# SL_LCD_SW_LED_2E.net
KiCad netlist of a schematic drawn in Altium Designer
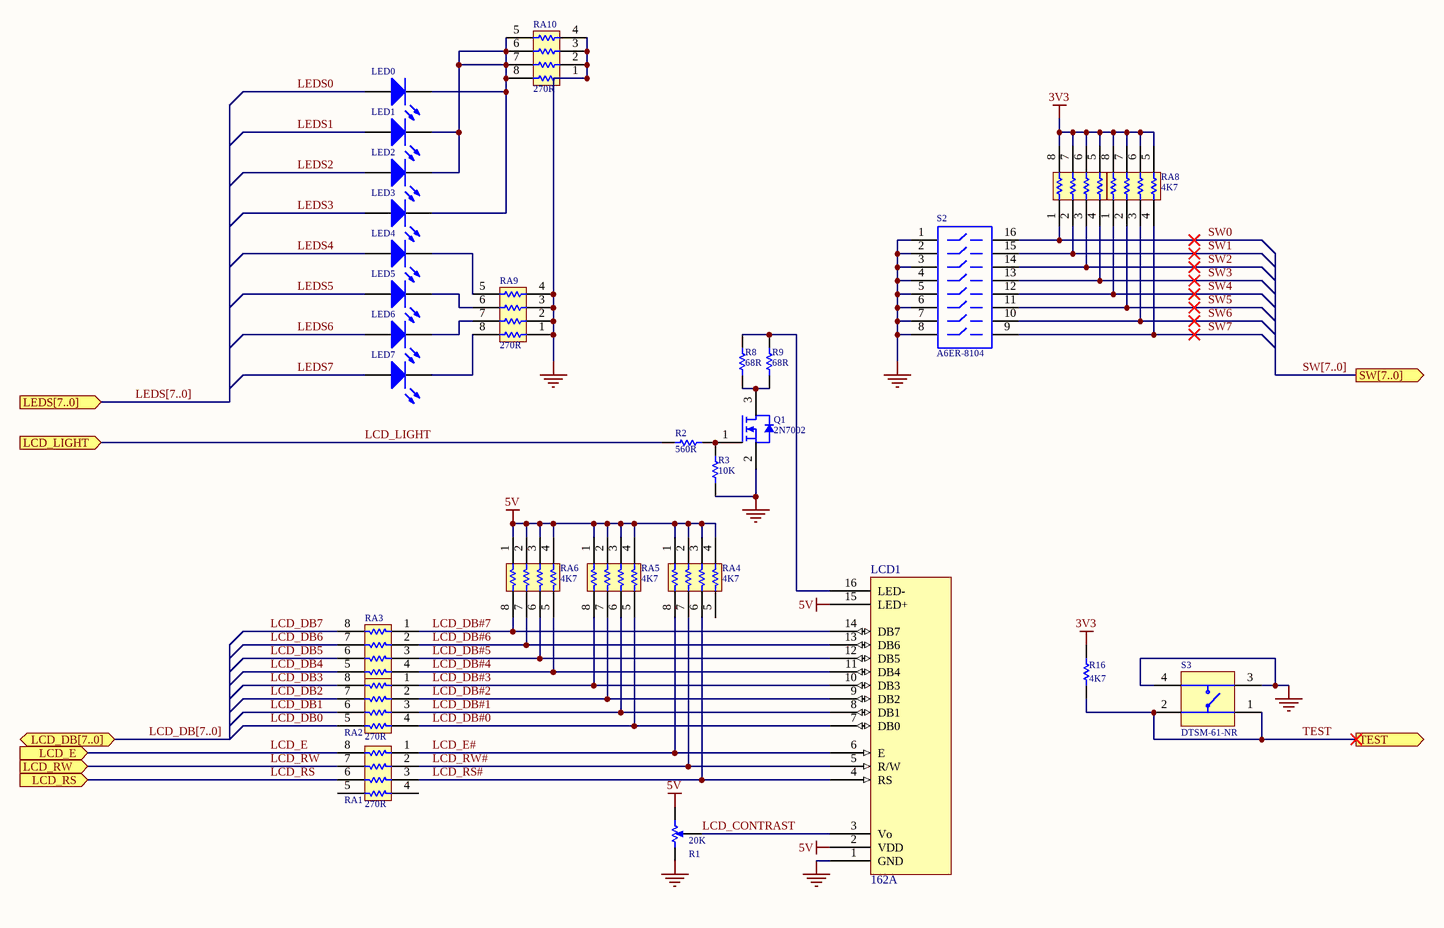
[diagram p0: SL_LCD_SW_LED_2E.SchDoc]

(export (version "E")
  (design (tool "Eeschema 10.0.6"))
  (components
    (comp (ref "LCD1")
      (value "162A")
      (footprint "Spirit_Level_Project:162A")
      (description "16 char * 2 line LCD character display with b/light")
      (libsource (lib "SpiritLevel_2E") (part "162A"))
    )
    (comp (ref "LED0")
      (value "HSMH-C170")
      (footprint "Spirit_Level_Project:SMD _LED")
      (description "Typical RED GaAs SMD LED Agilent make")
      (libsource (lib "SpiritLevel_2E") (part "HSMX-C670"))
    )
    (comp (ref "LED1")
      (value "HSMH-C170")
      (footprint "Spirit_Level_Project:SMD _LED")
      (description "Typical RED GaAs SMD LED Agilent make")
      (libsource (lib "SpiritLevel_2E") (part "HSMX-C670"))
    )
    (comp (ref "LED2")
      (value "HSMH-C170")
      (footprint "Spirit_Level_Project:SMD _LED")
      (description "Typical RED GaAs SMD LED Agilent make")
      (libsource (lib "SpiritLevel_2E") (part "HSMX-C670"))
    )
    (comp (ref "LED3")
      (value "HSMH-C170")
      (footprint "Spirit_Level_Project:SMD _LED")
      (description "Typical RED GaAs SMD LED Agilent make")
      (libsource (lib "SpiritLevel_2E") (part "HSMX-C670"))
    )
    (comp (ref "LED4")
      (value "HSMH-C170")
      (footprint "Spirit_Level_Project:SMD _LED")
      (description "Typical RED GaAs SMD LED Agilent make")
      (libsource (lib "SpiritLevel_2E") (part "HSMX-C670"))
    )
    (comp (ref "LED5")
      (value "HSMH-C170")
      (footprint "Spirit_Level_Project:SMD _LED")
      (description "Typical RED GaAs SMD LED Agilent make")
      (libsource (lib "SpiritLevel_2E") (part "HSMX-C670"))
    )
    (comp (ref "LED6")
      (value "HSMH-C170")
      (footprint "Spirit_Level_Project:SMD _LED")
      (description "Typical RED GaAs SMD LED Agilent make")
      (libsource (lib "SpiritLevel_2E") (part "HSMX-C670"))
    )
    (comp (ref "LED7")
      (value "HSMH-C170")
      (footprint "Spirit_Level_Project:SMD _LED")
      (description "Typical RED GaAs SMD LED Agilent make")
      (libsource (lib "SpiritLevel_2E") (part "HSMX-C670"))
    )
    (comp (ref "Q1")
      (value "2N7002")
      (footprint "Spirit_Level_Project:SO-G3")
      (description "N Channel Mosfet")
      (libsource (lib "SpiritLevel_2E") (part "2N7002"))
    )
    (comp (ref "R1")
      (value "20K")
      (footprint "Spirit_Level_Project:POT4MM-2")
      (description "Square Trimming Potentiometer")
      (libsource (lib "SpiritLevel_2E") (part "RPot SM"))
    )
    (comp (ref "R2")
      (value "560R")
      (footprint "CC2012-0805")
      (description "Resistor")
      (libsource (lib "SpiritLevel_2E") (part "RES"))
    )
    (comp (ref "R3")
      (value "10K")
      (footprint "CC2012-0805")
      (description "Resistor")
      (libsource (lib "SpiritLevel_2E") (part "RES"))
    )
    (comp (ref "R8")
      (value "68R")
      (footprint "CC2012-0805")
      (description "Resistor")
      (libsource (lib "") (part "RES_1"))
    )
    (comp (ref "R9")
      (value "68R")
      (footprint "CC2012-0805")
      (description "Resistor")
      (libsource (lib "") (part "RES_1"))
    )
    (comp (ref "R16")
      (value "4K7")
      (footprint "CC2012-0805")
      (description "Resistor")
      (libsource (lib "SpiritLevel_2E") (part "RES"))
    )
    (comp (ref "RA1")
      (value "270R")
      (footprint "Spirit_Level_Project:MNR34")
      (description "3216x4 Resistor Array")
      (libsource (lib "") (part "MNR34_1"))
    )
    (comp (ref "RA2")
      (value "270R")
      (footprint "Spirit_Level_Project:MNR34")
      (description "3216x4 Resistor Array")
      (libsource (lib "") (part "MNR34_1"))
    )
    (comp (ref "RA3")
      (value "270R")
      (footprint "Spirit_Level_Project:MNR34")
      (description "3216x4 Resistor Array")
      (libsource (lib "") (part "MNR34_1"))
    )
    (comp (ref "RA4")
      (value "4K7")
      (footprint "Spirit_Level_Project:MNR34T")
      (description "3216x4 Resistor Array")
      (libsource (lib "") (part "MNR34_2"))
    )
    (comp (ref "RA5")
      (value "4K7")
      (footprint "Spirit_Level_Project:MNR34T")
      (description "3216x4 Resistor Array")
      (libsource (lib "") (part "MNR34_2"))
    )
    (comp (ref "RA6")
      (value "4K7")
      (footprint "Spirit_Level_Project:MNR34T")
      (description "3216x4 Resistor Array")
      (libsource (lib "") (part "MNR34_2"))
    )
    (comp (ref "RA7")
      (value "4K7")
      (footprint "Spirit_Level_Project:MNR34T")
      (description "3216x4 Resistor Array")
      (libsource (lib "") (part "MNR34_3"))
    )
    (comp (ref "RA8")
      (value "4K7")
      (footprint "Spirit_Level_Project:MNR34T")
      (description "3216x4 Resistor Array")
      (libsource (lib "") (part "MNR34_3"))
    )
    (comp (ref "RA9")
      (value "270R")
      (footprint "Spirit_Level_Project:MNR34T")
      (description "3216x4 Resistor Array")
      (libsource (lib "SpiritLevel_2E") (part "MNR34"))
    )
    (comp (ref "RA10")
      (value "270R")
      (footprint "Spirit_Level_Project:MNR34T")
      (description "3216x4 Resistor Array")
      (libsource (lib "SpiritLevel_2E") (part "MNR34"))
    )
    (comp (ref "S2")
      (value "A6ER-8104")
      (footprint "Spirit_Level_Project:DIP-16-KEY")
      (description "DIP Switch Side actuator long liver Piano Key")
      (libsource (lib "SpiritLevel_2E") (part "A6ER-8104"))
    )
    (comp (ref "S3")
      (value "DTSM-61-NR")
      (footprint "Spirit_Level_Project:B3FS_SWITCH")
      (description "SPNA SMD Keyboard Switch")
      (libsource (lib "SpiritLevel_2E") (part "B3FS"))
    )
  )
  (nets
    (net (code "1") (name "/LCD_CONTRAST") (class "Default")
      (node (ref "LCD1") (pin "3") (pinfunction "Vo_3") (pintype "tri_state"))
      (node (ref "R1") (pin "W") (pintype "passive"))
    )
    (net (code "2") (name "/LCD_DB#0") (class "Default")
      (node (ref "LCD1") (pin "7") (pinfunction "DB0_7") (pintype "bidirectional"))
      (node (ref "RA2") (pin "4") (pintype "passive"))
      (node (ref "RA5") (pin "5") (pintype "passive"))
    )
    (net (code "3") (name "/LCD_DB#1") (class "Default")
      (node (ref "LCD1") (pin "8") (pinfunction "DB1_8") (pintype "bidirectional"))
      (node (ref "RA2") (pin "3") (pintype "passive"))
      (node (ref "RA5") (pin "6") (pintype "passive"))
    )
    (net (code "4") (name "/LCD_DB#2") (class "Default")
      (node (ref "LCD1") (pin "9") (pinfunction "DB2_9") (pintype "bidirectional"))
      (node (ref "RA2") (pin "2") (pintype "passive"))
      (node (ref "RA5") (pin "7") (pintype "passive"))
    )
    (net (code "5") (name "/LCD_DB#3") (class "Default")
      (node (ref "LCD1") (pin "10") (pinfunction "DB3_10") (pintype "bidirectional"))
      (node (ref "RA2") (pin "1") (pintype "passive"))
      (node (ref "RA5") (pin "8") (pintype "passive"))
    )
    (net (code "6") (name "/LCD_DB#4") (class "Default")
      (node (ref "LCD1") (pin "11") (pinfunction "DB4_11") (pintype "bidirectional"))
      (node (ref "RA3") (pin "4") (pintype "passive"))
      (node (ref "RA6") (pin "5") (pintype "passive"))
    )
    (net (code "7") (name "/LCD_DB#5") (class "Default")
      (node (ref "LCD1") (pin "12") (pinfunction "DB5_12") (pintype "bidirectional"))
      (node (ref "RA3") (pin "3") (pintype "passive"))
      (node (ref "RA6") (pin "6") (pintype "passive"))
    )
    (net (code "8") (name "/LCD_DB#6") (class "Default")
      (node (ref "LCD1") (pin "13") (pinfunction "DB6_13") (pintype "bidirectional"))
      (node (ref "RA3") (pin "2") (pintype "passive"))
      (node (ref "RA6") (pin "7") (pintype "passive"))
    )
    (net (code "9") (name "/LCD_DB#7") (class "Default")
      (node (ref "LCD1") (pin "14") (pinfunction "DB7_14") (pintype "bidirectional"))
      (node (ref "RA3") (pin "1") (pintype "passive"))
      (node (ref "RA6") (pin "8") (pintype "passive"))
    )
    (net (code "10") (name "/LCD_DB0") (class "Default") (node (ref "RA2") (pin "5") (pintype "passive")))
    (net (code "11") (name "/LCD_DB1") (class "Default") (node (ref "RA2") (pin "6") (pintype "passive")))
    (net (code "12") (name "/LCD_DB2") (class "Default") (node (ref "RA2") (pin "7") (pintype "passive")))
    (net (code "13") (name "/LCD_DB3") (class "Default") (node (ref "RA2") (pin "8") (pintype "passive")))
    (net (code "14") (name "/LCD_DB4") (class "Default") (node (ref "RA3") (pin "5") (pintype "passive")))
    (net (code "15") (name "/LCD_DB5") (class "Default") (node (ref "RA3") (pin "6") (pintype "passive")))
    (net (code "16") (name "/LCD_DB6") (class "Default") (node (ref "RA3") (pin "7") (pintype "passive")))
    (net (code "17") (name "/LCD_DB7") (class "Default") (node (ref "RA3") (pin "8") (pintype "passive")))
    (net (code "19") (name "/LCD_E") (class "Default") (node (ref "RA1") (pin "8") (pintype "passive")))
    (net (code "20") (name "/LCD_E#") (class "Default")
      (node (ref "LCD1") (pin "6") (pinfunction "E_6") (pintype "input"))
      (node (ref "RA1") (pin "1") (pintype "passive"))
      (node (ref "RA4") (pin "8") (pintype "passive"))
    )
    (net (code "21") (name "/LCD_LIGHT") (class "Default")
      (node (ref "R2") (pin "1") (pinfunction "1_1") (pintype "passive"))
    )
    (net (code "22") (name "/LCD_RS") (class "Default") (node (ref "RA1") (pin "6") (pintype "passive")))
    (net (code "23") (name "/LCD_RS#") (class "Default")
      (node (ref "LCD1") (pin "4") (pinfunction "RS_4") (pintype "input"))
      (node (ref "RA1") (pin "3") (pintype "passive"))
      (node (ref "RA4") (pin "6") (pintype "passive"))
    )
    (net (code "24") (name "/LCD_RW") (class "Default") (node (ref "RA1") (pin "7") (pintype "passive")))
    (net (code "25") (name "/LCD_RW#") (class "Default")
      (node (ref "LCD1") (pin "5") (pinfunction "R/W_5") (pintype "input"))
      (node (ref "RA1") (pin "2") (pintype "passive"))
      (node (ref "RA4") (pin "7") (pintype "passive"))
    )
    (net (code "26") (name "/LEDS0") (class "Default")
      (node (ref "LED0") (pin "1") (pinfunction "A_1") (pintype "passive"))
    )
    (net (code "27") (name "/LEDS1") (class "Default")
      (node (ref "LED1") (pin "1") (pinfunction "A_1") (pintype "passive"))
    )
    (net (code "28") (name "/LEDS2") (class "Default")
      (node (ref "LED2") (pin "1") (pinfunction "A_1") (pintype "passive"))
    )
    (net (code "29") (name "/LEDS3") (class "Default")
      (node (ref "LED3") (pin "1") (pinfunction "A_1") (pintype "passive"))
    )
    (net (code "30") (name "/LEDS4") (class "Default")
      (node (ref "LED4") (pin "1") (pinfunction "A_1") (pintype "passive"))
    )
    (net (code "31") (name "/LEDS5") (class "Default")
      (node (ref "LED5") (pin "1") (pinfunction "A_1") (pintype "passive"))
    )
    (net (code "32") (name "/LEDS6") (class "Default")
      (node (ref "LED6") (pin "1") (pinfunction "A_1") (pintype "passive"))
    )
    (net (code "33") (name "/LEDS7") (class "Default")
      (node (ref "LED7") (pin "1") (pinfunction "A_1") (pintype "passive"))
    )
    (net (code "35") (name "/SW0") (class "Default")
      (node (ref "RA7") (pin "1") (pintype "passive"))
      (node (ref "S2") (pin "16") (pinfunction "16_16") (pintype "passive"))
    )
    (net (code "36") (name "/SW1") (class "Default")
      (node (ref "RA7") (pin "2") (pintype "passive"))
      (node (ref "S2") (pin "15") (pinfunction "15_15") (pintype "passive"))
    )
    (net (code "37") (name "/SW2") (class "Default")
      (node (ref "RA7") (pin "3") (pintype "passive"))
      (node (ref "S2") (pin "14") (pinfunction "14_14") (pintype "passive"))
    )
    (net (code "38") (name "/SW3") (class "Default")
      (node (ref "RA7") (pin "4") (pintype "passive"))
      (node (ref "S2") (pin "13") (pinfunction "13_13") (pintype "passive"))
    )
    (net (code "39") (name "/SW4") (class "Default")
      (node (ref "RA8") (pin "1") (pintype "passive"))
      (node (ref "S2") (pin "12") (pinfunction "12_12") (pintype "passive"))
    )
    (net (code "40") (name "/SW5") (class "Default")
      (node (ref "RA8") (pin "2") (pintype "passive"))
      (node (ref "S2") (pin "11") (pinfunction "11_11") (pintype "passive"))
    )
    (net (code "41") (name "/SW6") (class "Default")
      (node (ref "RA8") (pin "3") (pintype "passive"))
      (node (ref "S2") (pin "10") (pinfunction "10_10") (pintype "passive"))
    )
    (net (code "42") (name "/SW7") (class "Default")
      (node (ref "RA8") (pin "4") (pintype "passive"))
      (node (ref "S2") (pin "9") (pinfunction "9_9") (pintype "passive"))
    )
    (net (code "44") (name "/TEST") (class "Default")
      (node (ref "R16") (pin "2") (pinfunction "2_2") (pintype "passive"))
      (node (ref "S3") (pin "1") (pinfunction "1_1") (pintype "passive"))
      (node (ref "S3") (pin "2") (pinfunction "2_2") (pintype "passive"))
    )
    (net (code "45") (name "3V3") (class "Default")
      (node (ref "R16") (pin "1") (pinfunction "1_1") (pintype "passive"))
      (node (ref "RA7") (pin "5") (pintype "passive"))
      (node (ref "RA7") (pin "6") (pintype "passive"))
      (node (ref "RA7") (pin "7") (pintype "passive"))
      (node (ref "RA7") (pin "8") (pintype "passive"))
      (node (ref "RA8") (pin "5") (pintype "passive"))
      (node (ref "RA8") (pin "6") (pintype "passive"))
      (node (ref "RA8") (pin "7") (pintype "passive"))
      (node (ref "RA8") (pin "8") (pintype "passive"))
    )
    (net (code "46") (name "5V") (class "Default")
      (node (ref "LCD1") (pin "15") (pinfunction "LED+_15") (pintype "power_in"))
      (node (ref "LCD1") (pin "2") (pinfunction "VDD_2") (pintype "power_in"))
      (node (ref "R1") (pin "CW") (pinfunction "+_CW") (pintype "passive"))
      (node (ref "RA4") (pin "1") (pintype "passive"))
      (node (ref "RA4") (pin "2") (pintype "passive"))
      (node (ref "RA4") (pin "3") (pintype "passive"))
      (node (ref "RA4") (pin "4") (pintype "passive"))
      (node (ref "RA5") (pin "1") (pintype "passive"))
      (node (ref "RA5") (pin "2") (pintype "passive"))
      (node (ref "RA5") (pin "3") (pintype "passive"))
      (node (ref "RA5") (pin "4") (pintype "passive"))
      (node (ref "RA6") (pin "1") (pintype "passive"))
      (node (ref "RA6") (pin "2") (pintype "passive"))
      (node (ref "RA6") (pin "3") (pintype "passive"))
      (node (ref "RA6") (pin "4") (pintype "passive"))
    )
    (net (code "47") (name "GND") (class "Default")
      (node (ref "LCD1") (pin "1") (pinfunction "GND_1") (pintype "power_in"))
      (node (ref "Q1") (pin "2") (pintype "passive"))
      (node (ref "R1") (pin "CCW") (pinfunction "-_CCW") (pintype "passive"))
      (node (ref "R3") (pin "1") (pinfunction "1_1") (pintype "passive"))
      (node (ref "RA10") (pin "1") (pintype "passive"))
      (node (ref "RA10") (pin "2") (pintype "passive"))
      (node (ref "RA10") (pin "3") (pintype "passive"))
      (node (ref "RA10") (pin "4") (pintype "passive"))
      (node (ref "RA9") (pin "1") (pintype "passive"))
      (node (ref "RA9") (pin "2") (pintype "passive"))
      (node (ref "RA9") (pin "3") (pintype "passive"))
      (node (ref "RA9") (pin "4") (pintype "passive"))
      (node (ref "S2") (pin "1") (pinfunction "1_1") (pintype "passive"))
      (node (ref "S2") (pin "2") (pinfunction "2_2") (pintype "passive"))
      (node (ref "S2") (pin "3") (pinfunction "3_3") (pintype "passive"))
      (node (ref "S2") (pin "4") (pinfunction "4_4") (pintype "passive"))
      (node (ref "S2") (pin "5") (pinfunction "5_5") (pintype "passive"))
      (node (ref "S2") (pin "6") (pinfunction "6_6") (pintype "passive"))
      (node (ref "S2") (pin "7") (pinfunction "7_7") (pintype "passive"))
      (node (ref "S2") (pin "8") (pinfunction "8_8") (pintype "passive"))
      (node (ref "S3") (pin "3") (pinfunction "3_3") (pintype "passive"))
      (node (ref "S3") (pin "4") (pinfunction "4_4") (pintype "passive"))
    )
    (net (code "48") (name "Net-(LCD1-LED-)") (class "Default")
      (node (ref "LCD1") (pin "16") (pinfunction "LED-_16") (pintype "power_in"))
      (node (ref "R8") (pin "1") (pinfunction "1_1") (pintype "passive"))
      (node (ref "R9") (pin "1") (pinfunction "1_1") (pintype "passive"))
    )
    (net (code "49") (name "Net-(LED0-K)") (class "Default")
      (node (ref "LED0") (pin "2") (pinfunction "K_2") (pintype "passive"))
      (node (ref "LED1") (pin "2") (pinfunction "K_2") (pintype "passive"))
      (node (ref "LED2") (pin "2") (pinfunction "K_2") (pintype "passive"))
      (node (ref "LED3") (pin "2") (pinfunction "K_2") (pintype "passive"))
      (node (ref "RA10") (pin "5") (pintype "passive"))
      (node (ref "RA10") (pin "6") (pintype "passive"))
      (node (ref "RA10") (pin "7") (pintype "passive"))
      (node (ref "RA10") (pin "8") (pintype "passive"))
    )
    (net (code "50") (name "Net-(LED4-K)") (class "Default")
      (node (ref "LED4") (pin "2") (pinfunction "K_2") (pintype "passive"))
      (node (ref "RA9") (pin "5") (pintype "passive"))
    )
    (net (code "51") (name "Net-(LED5-K)") (class "Default")
      (node (ref "LED5") (pin "2") (pinfunction "K_2") (pintype "passive"))
      (node (ref "RA9") (pin "6") (pintype "passive"))
    )
    (net (code "52") (name "Net-(LED6-K)") (class "Default")
      (node (ref "LED6") (pin "2") (pinfunction "K_2") (pintype "passive"))
      (node (ref "RA9") (pin "7") (pintype "passive"))
    )
    (net (code "53") (name "Net-(LED7-K)") (class "Default")
      (node (ref "LED7") (pin "2") (pinfunction "K_2") (pintype "passive"))
      (node (ref "RA9") (pin "8") (pintype "passive"))
    )
    (net (code "54") (name "Net-(Q1-Pad1)") (class "Default")
      (node (ref "Q1") (pin "1") (pintype "passive"))
      (node (ref "R2") (pin "2") (pinfunction "2_2") (pintype "passive"))
      (node (ref "R3") (pin "2") (pinfunction "2_2") (pintype "passive"))
    )
    (net (code "55") (name "Net-(Q1-Pad3)") (class "Default")
      (node (ref "Q1") (pin "3") (pintype "passive"))
      (node (ref "R8") (pin "2") (pinfunction "2_2") (pintype "passive"))
      (node (ref "R9") (pin "2") (pinfunction "2_2") (pintype "passive"))
    )
    (net (code "56") (name "unconnected-(RA1-Pad4)") (class "Default")
      (node (ref "RA1") (pin "4") (pintype "passive"))
    )
    (net (code "57") (name "unconnected-(RA1-Pad5)") (class "Default")
      (node (ref "RA1") (pin "5") (pintype "passive"))
    )
    (net (code "58") (name "unconnected-(RA4-Pad5)") (class "Default")
      (node (ref "RA4") (pin "5") (pintype "passive"))
    )
  )
)
